# Own_21700_Board_Plus_pro_v1_1_Final_AR.net
KiCad netlist of a schematic drawn in EAGLE
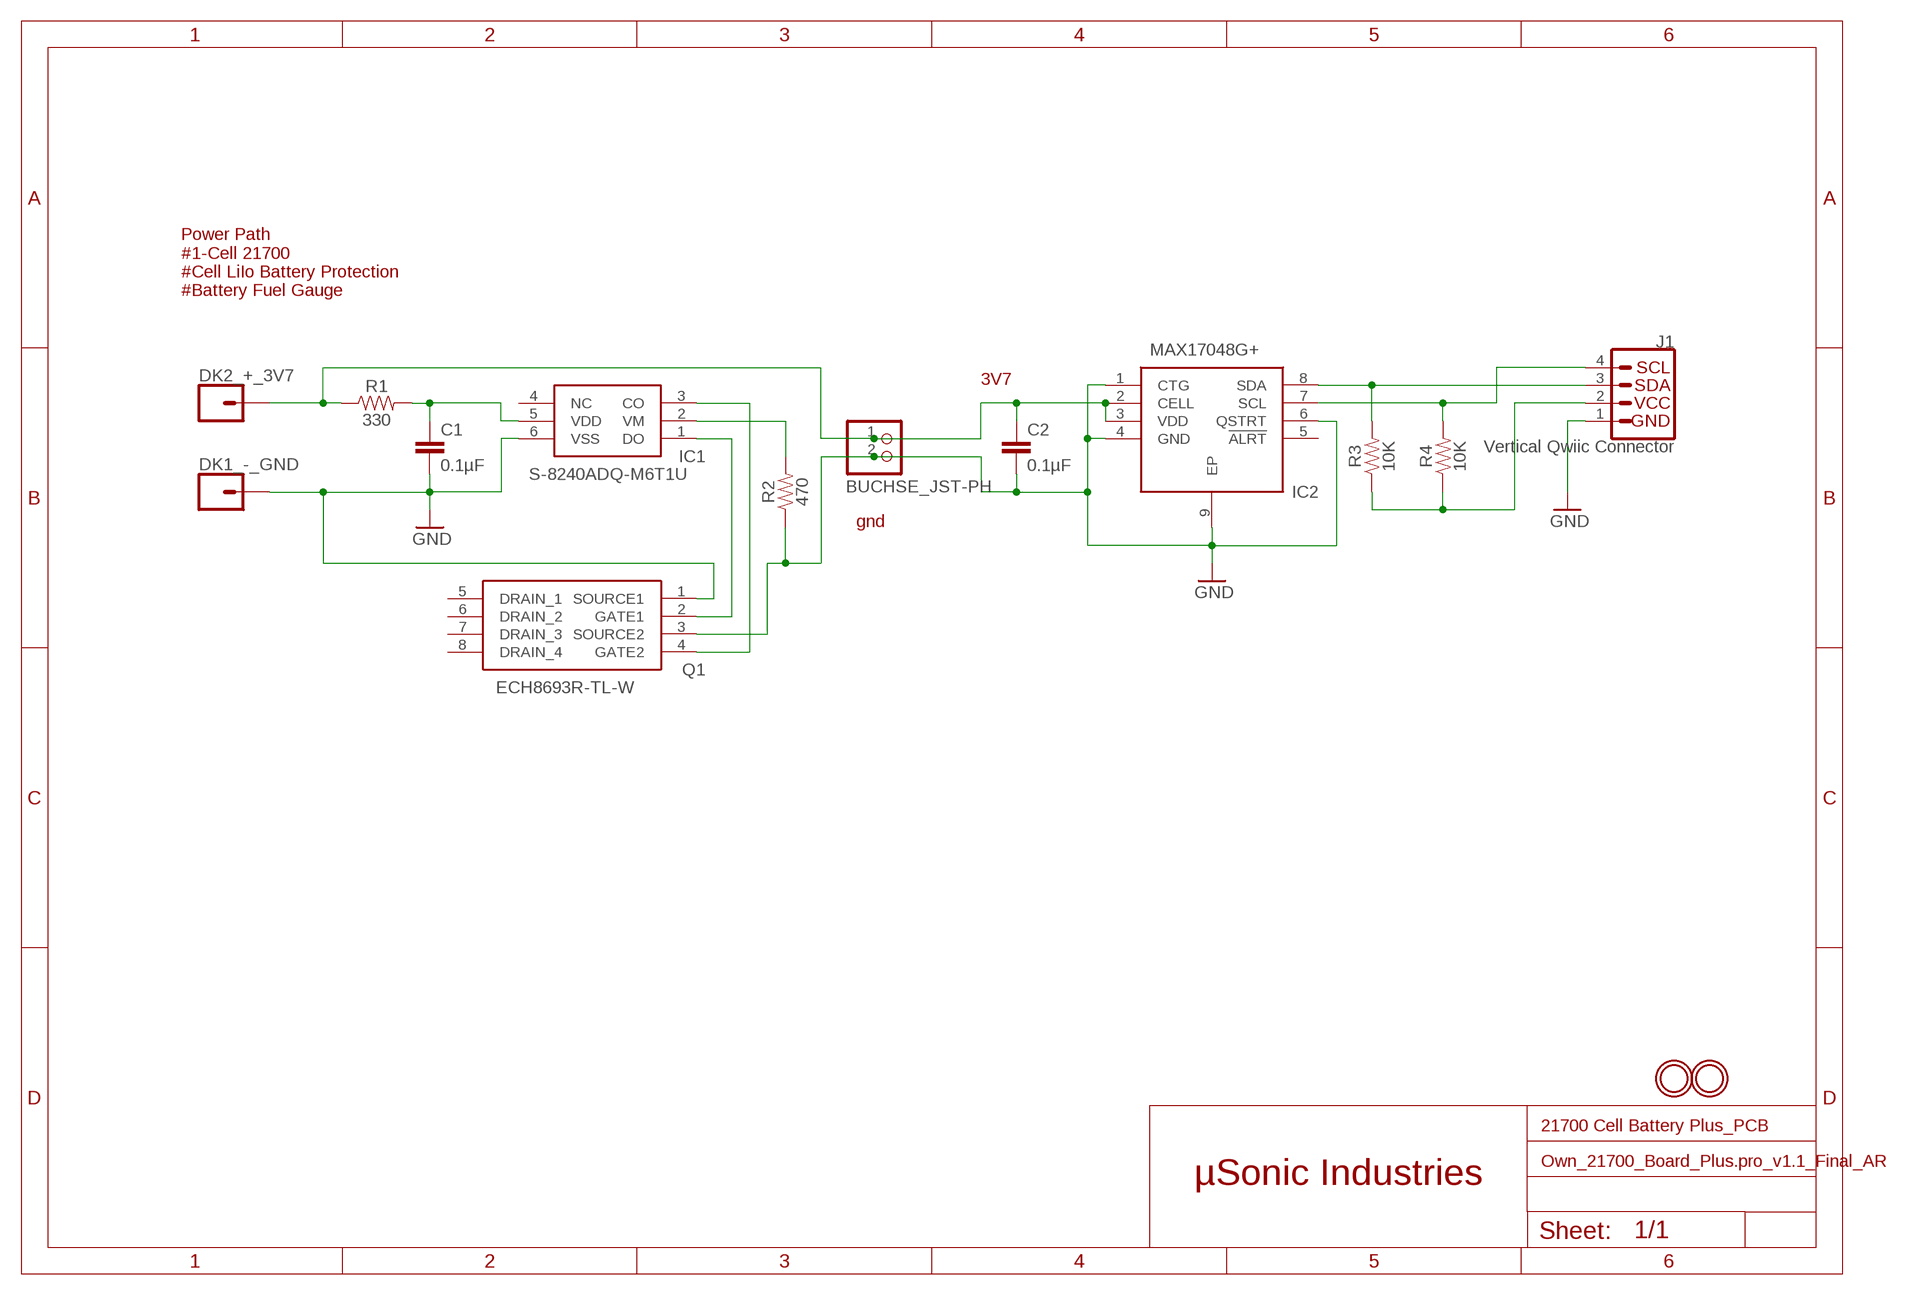
[diagram p0: schematic, sheet 1]

(export (version "E")
  (design (tool "Eeschema 10.0.6"))
  (components
    (comp (ref "BUCHSE_JST-PH")
      (value "JST_2PINOWN")
      (footprint "eagle-import:JST-PH-2-THMOWN")
      (libsource (lib "eagle-import") (part "JST_2PINOWN"))
    )
    (comp (ref "C1")
      (value "0.1µF")
      (footprint "eagle-import:0805")
      (libsource (lib "eagle-import") (part "0.33UF/330NF-0805-50V-10%"))
    )
    (comp (ref "C2")
      (value "0.1µF")
      (footprint "eagle-import:0805")
      (libsource (lib "eagle-import") (part "0.33UF/330NF-0805-50V-10%"))
    )
    (comp (ref "DK1_-_GND")
      (value "CONN_01PTH_2MM")
      (footprint "eagle-import:1X01_2MM")
      (libsource (lib "eagle-import") (part "CONN_01PTH_2MM"))
    )
    (comp (ref "DK2_+_3V7")
      (value "CONN_01PTH_2MM")
      (footprint "eagle-import:1X01_2MM")
      (libsource (lib "eagle-import") (part "CONN_01PTH_2MM"))
    )
    (comp (ref "IC1")
      (value "S-8240ADQ-M6T1U")
      (footprint "eagle-import:SOT95P275X135-6N")
      (fields (field (name "MOUSER_PART_NUMBER") "628-S-8240ADQ-M6T1U"))
      (libsource (lib "eagle-import") (part "S-8240ADQ-M6T1U"))
    )
    (comp (ref "IC2")
      (value "MAX17048G+")
      (footprint "eagle-import:SON50P200X200X80-9N")
      (fields (field (name "MOUSER_PART_NUMBER") "700-MAX17048G+"))
      (libsource (lib "eagle-import") (part "MAX17048G+"))
    )
    (comp (ref "J1")
      (value "Vertical Qwiic Connector")
      (footprint "eagle-import:JST04_1MM_VERT")
      (libsource (lib "eagle-import") (part "QWIIC_CONNECTOROWN"))
    )
    (comp (ref "Q1")
      (value "ECH8693R-TL-W")
      (footprint "eagle-import:SOTFL65P280X95-8N")
      (fields (field (name "MOUSER_PART_NUMBER") "863-ECH8693R-TL-W"))
      (libsource (lib "eagle-import") (part "ECH8693R-TL-W"))
    )
    (comp (ref "R1")
      (value "330")
      (footprint "eagle-import:0805")
      (libsource (lib "eagle-import") (part "RESISTOR0805"))
    )
    (comp (ref "R2")
      (value "470")
      (footprint "eagle-import:0805")
      (libsource (lib "eagle-import") (part "RESISTOR0805"))
    )
    (comp (ref "R3")
      (value "10K")
      (footprint "eagle-import:0805")
      (libsource (lib "eagle-import") (part "RESISTOR0805"))
    )
    (comp (ref "R4")
      (value "10K")
      (footprint "eagle-import:0805")
      (libsource (lib "eagle-import") (part "RESISTOR0805"))
    )
    (comp (ref "U$3")
      (value "MOUNTINGHOLE2.5")
      (footprint "eagle-import:MOUNTINGHOLE_2.5_PLATED")
      (libsource (lib "eagle-import") (part "MOUNTINGHOLE2.5"))
    )
    (comp (ref "U$5")
      (value "MOUNTINGHOLE2.5")
      (footprint "eagle-import:MOUNTINGHOLE_2.5_PLATED")
      (libsource (lib "eagle-import") (part "MOUNTINGHOLE2.5"))
    )
  )
  (nets
    (net (code "1") (name "GND") (class "Default")
      (node (ref "BUCHSE_JST-PH") (pin "2") (pinfunction "1_2") (pintype "passive"))
      (node (ref "C1") (pin "2") (pinfunction "2_2") (pintype "passive"))
      (node (ref "C2") (pin "2") (pinfunction "2_2") (pintype "passive"))
      (node (ref "DK1_-_GND") (pin "1") (pinfunction "1_1") (pintype "passive"))
      (node (ref "IC1") (pin "6") (pinfunction "VSS_6") (pintype "bidirectional"))
      (node (ref "IC2") (pin "1") (pinfunction "CTG_1") (pintype "bidirectional"))
      (node (ref "IC2") (pin "4") (pinfunction "GND_4") (pintype "bidirectional"))
      (node (ref "IC2") (pin "6") (pinfunction "QSTRT_6") (pintype "bidirectional"))
      (node (ref "IC2") (pin "9") (pinfunction "EP_9") (pintype "bidirectional"))
      (node (ref "J1") (pin "1") (pinfunction "1_1") (pintype "power_in"))
      (node (ref "Q1") (pin "1") (pinfunction "SOURCE1_1") (pintype "bidirectional"))
      (node (ref "Q1") (pin "3") (pinfunction "SOURCE2_3") (pintype "bidirectional"))
      (node (ref "R2") (pin "1") (pinfunction "1_1") (pintype "passive"))
    )
    (net (code "2") (name "Net-(BUCHSE_JST-PH-2)") (class "Default")
      (node (ref "BUCHSE_JST-PH") (pin "1") (pinfunction "2_1") (pintype "passive"))
      (node (ref "C2") (pin "1") (pinfunction "1_1") (pintype "passive"))
      (node (ref "DK2_+_3V7") (pin "1") (pinfunction "1_1") (pintype "passive"))
      (node (ref "IC2") (pin "2") (pinfunction "CELL_2") (pintype "bidirectional"))
      (node (ref "IC2") (pin "3") (pinfunction "VDD_3") (pintype "bidirectional"))
      (node (ref "R1") (pin "1") (pinfunction "1_1") (pintype "passive"))
    )
    (net (code "3") (name "Net-(IC1-CO)") (class "Default")
      (node (ref "IC1") (pin "3") (pinfunction "CO_3") (pintype "bidirectional"))
      (node (ref "Q1") (pin "4") (pinfunction "GATE2_4") (pintype "bidirectional"))
    )
    (net (code "4") (name "Net-(IC1-DO)") (class "Default")
      (node (ref "IC1") (pin "1") (pinfunction "DO_1") (pintype "bidirectional"))
      (node (ref "Q1") (pin "2") (pinfunction "GATE1_2") (pintype "bidirectional"))
    )
    (net (code "5") (name "Net-(IC1-VDD)") (class "Default")
      (node (ref "C1") (pin "1") (pinfunction "1_1") (pintype "passive"))
      (node (ref "IC1") (pin "5") (pinfunction "VDD_5") (pintype "bidirectional"))
      (node (ref "R1") (pin "2") (pinfunction "2_2") (pintype "passive"))
    )
    (net (code "6") (name "Net-(IC1-VM)") (class "Default")
      (node (ref "IC1") (pin "2") (pinfunction "VM_2") (pintype "bidirectional"))
      (node (ref "R2") (pin "2") (pinfunction "2_2") (pintype "passive"))
    )
    (net (code "7") (name "Net-(IC2-SCL)") (class "Default")
      (node (ref "IC2") (pin "7") (pinfunction "SCL_7") (pintype "bidirectional"))
      (node (ref "J1") (pin "4") (pinfunction "4_4") (pintype "passive"))
      (node (ref "R4") (pin "2") (pinfunction "2_2") (pintype "passive"))
    )
    (net (code "8") (name "Net-(IC2-SDA)") (class "Default")
      (node (ref "IC2") (pin "8") (pinfunction "SDA_8") (pintype "bidirectional"))
      (node (ref "J1") (pin "3") (pinfunction "3_3") (pintype "passive"))
      (node (ref "R3") (pin "2") (pinfunction "2_2") (pintype "passive"))
    )
    (net (code "9") (name "Net-(J1-Pad2)") (class "Default")
      (node (ref "J1") (pin "2") (pinfunction "2_2") (pintype "power_in"))
      (node (ref "R3") (pin "1") (pinfunction "1_1") (pintype "passive"))
      (node (ref "R4") (pin "1") (pinfunction "1_1") (pintype "passive"))
    )
    (net (code "10") (name "unconnected-(IC1-NC-Pad4)") (class "Default")
      (node (ref "IC1") (pin "4") (pinfunction "NC_4") (pintype "no_connect"))
    )
    (net (code "11") (name "unconnected-(IC2-~{ALRT}-Pad5)") (class "Default")
      (node (ref "IC2") (pin "5") (pinfunction "~{ALRT}_5") (pintype "bidirectional"))
    )
    (net (code "12") (name "unconnected-(Q1-DRAIN_1-Pad5)") (class "Default")
      (node (ref "Q1") (pin "5") (pinfunction "DRAIN_1_5") (pintype "bidirectional"))
    )
    (net (code "13") (name "unconnected-(Q1-DRAIN_2-Pad6)") (class "Default")
      (node (ref "Q1") (pin "6") (pinfunction "DRAIN_2_6") (pintype "bidirectional"))
    )
    (net (code "14") (name "unconnected-(Q1-DRAIN_3-Pad7)") (class "Default")
      (node (ref "Q1") (pin "7") (pinfunction "DRAIN_3_7") (pintype "bidirectional"))
    )
    (net (code "15") (name "unconnected-(Q1-DRAIN_4-Pad8)") (class "Default")
      (node (ref "Q1") (pin "8") (pinfunction "DRAIN_4_8") (pintype "bidirectional"))
    )
  )
)
